# PowerBoardConnector.net
KiCad netlist of a schematic drawn in Altium Designer
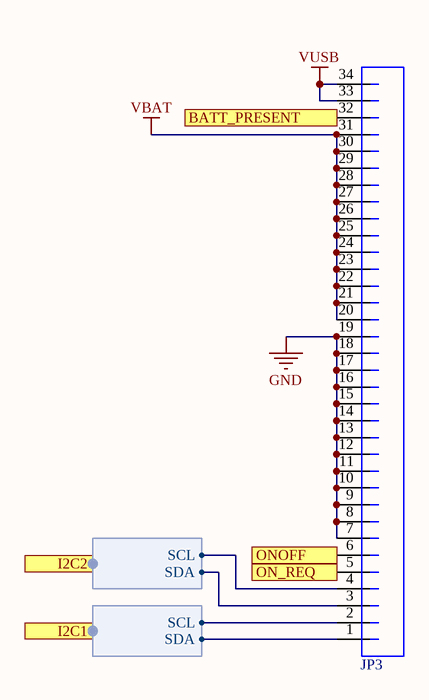
[diagram p0: PowerBoardConnector.SchDoc]

(export (version "E")
  (design (tool "Eeschema 10.0.6"))
  (components
    (comp (ref "JP3")
      (value "MOLEX_FFC-FPC_34")
      (footprint "MOLEX-FFC-FPC-0.5MM-34")
      (fields (field (name "MANUFACTURER") "Molex") (field (name "PARTNUMBER") "51296-3494"))
      (libsource (lib "Connectors") (part "MOLEX_FFC-FPC_34"))
    )
  )
  (nets
    (net (code "2") (name "/BATT_PRESENT") (class "Default")
      (node (ref "JP3") (pin "32") (pinfunction "32_32") (pintype "passive"))
    )
    (net (code "3") (name "/ONOFF") (class "Default")
      (node (ref "JP3") (pin "6") (pinfunction "6_6") (pintype "passive"))
    )
    (net (code "4") (name "/ON_REQ") (class "Default")
      (node (ref "JP3") (pin "5") (pinfunction "5_5") (pintype "passive"))
    )
    (net (code "6") (name "GND") (class "Default")
      (node (ref "JP3") (pin "10") (pinfunction "10_10") (pintype "passive"))
      (node (ref "JP3") (pin "11") (pinfunction "11_11") (pintype "passive"))
      (node (ref "JP3") (pin "12") (pinfunction "12_12") (pintype "passive"))
      (node (ref "JP3") (pin "13") (pinfunction "13_13") (pintype "passive"))
      (node (ref "JP3") (pin "14") (pinfunction "14_14") (pintype "passive"))
      (node (ref "JP3") (pin "15") (pinfunction "15_15") (pintype "passive"))
      (node (ref "JP3") (pin "16") (pinfunction "16_16") (pintype "passive"))
      (node (ref "JP3") (pin "17") (pinfunction "17_17") (pintype "passive"))
      (node (ref "JP3") (pin "18") (pinfunction "18_18") (pintype "passive"))
      (node (ref "JP3") (pin "19") (pinfunction "19_19") (pintype "passive"))
      (node (ref "JP3") (pin "7") (pinfunction "7_7") (pintype "passive"))
      (node (ref "JP3") (pin "8") (pinfunction "8_8") (pintype "passive"))
      (node (ref "JP3") (pin "9") (pinfunction "9_9") (pintype "passive"))
    )
    (net (code "7") (name "VBAT") (class "Default")
      (node (ref "JP3") (pin "20") (pinfunction "20_20") (pintype "passive"))
      (node (ref "JP3") (pin "21") (pinfunction "21_21") (pintype "passive"))
      (node (ref "JP3") (pin "22") (pinfunction "22_22") (pintype "passive"))
      (node (ref "JP3") (pin "23") (pinfunction "23_23") (pintype "passive"))
      (node (ref "JP3") (pin "24") (pinfunction "24_24") (pintype "passive"))
      (node (ref "JP3") (pin "25") (pinfunction "25_25") (pintype "passive"))
      (node (ref "JP3") (pin "26") (pinfunction "26_26") (pintype "passive"))
      (node (ref "JP3") (pin "27") (pinfunction "27_27") (pintype "passive"))
      (node (ref "JP3") (pin "28") (pinfunction "28_28") (pintype "passive"))
      (node (ref "JP3") (pin "29") (pinfunction "29_29") (pintype "passive"))
      (node (ref "JP3") (pin "30") (pinfunction "30_30") (pintype "passive"))
      (node (ref "JP3") (pin "31") (pinfunction "31_31") (pintype "passive"))
    )
    (net (code "8") (name "VUSB") (class "Default")
      (node (ref "JP3") (pin "33") (pinfunction "33_33") (pintype "passive"))
      (node (ref "JP3") (pin "34") (pinfunction "34_34") (pintype "passive"))
    )
    (net (code "9") (name "unconnected-(JP3-Pad1)") (class "Default")
      (node (ref "JP3") (pin "1") (pinfunction "1_1") (pintype "passive"))
    )
    (net (code "10") (name "unconnected-(JP3-Pad2)") (class "Default")
      (node (ref "JP3") (pin "2") (pinfunction "2_2") (pintype "passive"))
    )
    (net (code "11") (name "unconnected-(JP3-Pad3)") (class "Default")
      (node (ref "JP3") (pin "3") (pinfunction "3_3") (pintype "passive"))
    )
    (net (code "12") (name "unconnected-(JP3-Pad4)") (class "Default")
      (node (ref "JP3") (pin "4") (pinfunction "4_4") (pintype "passive"))
    )
  )
)
